# dc_motor.net
KiCad netlist of a schematic drawn in EAGLE
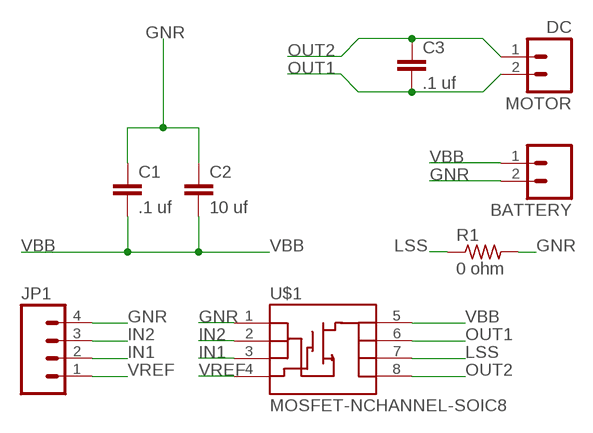
[diagram p0: schematic, sheet 1]

(export (version "E")
  (design (tool "Eeschema 10.0.6"))
  (components
    (comp (ref "BATTERY")
      (value "M02")
      (footprint "eagle-import:1X02_LONGPADS")
      (libsource (lib "eagle-import") (part "M02"))
    )
    (comp (ref "C1")
      (value ".1 uf")
      (footprint "eagle-import:1206")
      (libsource (lib "eagle-import") (part "CAP1206"))
    )
    (comp (ref "C2")
      (value "10 uf")
      (footprint "eagle-import:1206")
      (libsource (lib "eagle-import") (part "CAP1206"))
    )
    (comp (ref "C3")
      (value ".1 uf")
      (footprint "eagle-import:1206")
      (libsource (lib "eagle-import") (part "CAP1206"))
    )
    (comp (ref "JP1")
      (value "M04LONGPADS")
      (footprint "eagle-import:1X04_LONGPADS")
      (libsource (lib "eagle-import") (part "M04LONGPADS"))
    )
    (comp (ref "MOTOR")
      (value "DC")
      (footprint "eagle-import:1X02_LONGPADS")
      (libsource (lib "eagle-import") (part "M02"))
    )
    (comp (ref "R1")
      (value "0 ohm")
      (footprint "eagle-import:1206")
      (libsource (lib "eagle-import") (part "RESISTOR1206"))
    )
    (comp (ref "U$1")
      (value "MOSFET-NCHANNEL-SOIC8")
      (footprint "eagle-import:SO08")
      (libsource (lib "eagle-import") (part "MOSFET-NCHANNEL-SOIC8"))
    )
  )
  (nets
    (net (code "1") (name "/GNR") (class "Default")
      (node (ref "BATTERY") (pin "2") (pinfunction "2_2") (pintype "passive"))
      (node (ref "C1") (pin "1") (pinfunction "1_1") (pintype "passive"))
      (node (ref "C2") (pin "1") (pinfunction "1_1") (pintype "passive"))
      (node (ref "JP1") (pin "4") (pinfunction "4_4") (pintype "passive"))
      (node (ref "R1") (pin "2") (pinfunction "2_2") (pintype "passive"))
      (node (ref "U$1") (pin "1") (pinfunction "S_1") (pintype "bidirectional"))
    )
    (net (code "2") (name "/IN1") (class "Default")
      (node (ref "JP1") (pin "2") (pinfunction "2_2") (pintype "passive"))
      (node (ref "U$1") (pin "3") (pinfunction "S_3") (pintype "bidirectional"))
    )
    (net (code "3") (name "/IN2") (class "Default")
      (node (ref "JP1") (pin "3") (pinfunction "3_3") (pintype "passive"))
      (node (ref "U$1") (pin "2") (pinfunction "S_2") (pintype "bidirectional"))
    )
    (net (code "4") (name "/LSS") (class "Default")
      (node (ref "R1") (pin "1") (pinfunction "1_1") (pintype "passive"))
      (node (ref "U$1") (pin "7") (pinfunction "D_7") (pintype "bidirectional"))
    )
    (net (code "5") (name "/OUT1") (class "Default")
      (node (ref "C3") (pin "2") (pinfunction "2_2") (pintype "passive"))
      (node (ref "MOTOR") (pin "2") (pinfunction "2_2") (pintype "passive"))
      (node (ref "U$1") (pin "6") (pinfunction "D_6") (pintype "bidirectional"))
    )
    (net (code "6") (name "/OUT2") (class "Default")
      (node (ref "C3") (pin "1") (pinfunction "1_1") (pintype "passive"))
      (node (ref "MOTOR") (pin "1") (pinfunction "1_1") (pintype "passive"))
      (node (ref "U$1") (pin "8") (pinfunction "D_8") (pintype "bidirectional"))
    )
    (net (code "7") (name "/VBB") (class "Default")
      (node (ref "BATTERY") (pin "1") (pinfunction "1_1") (pintype "passive"))
      (node (ref "C1") (pin "2") (pinfunction "2_2") (pintype "passive"))
      (node (ref "C2") (pin "2") (pinfunction "2_2") (pintype "passive"))
      (node (ref "U$1") (pin "5") (pinfunction "D_5") (pintype "bidirectional"))
    )
    (net (code "8") (name "/VREF") (class "Default")
      (node (ref "JP1") (pin "1") (pinfunction "1_1") (pintype "passive"))
      (node (ref "U$1") (pin "4") (pinfunction "G_4") (pintype "bidirectional"))
    )
  )
)
